# RH001_2.net
KiCad netlist of a schematic drawn in EAGLE
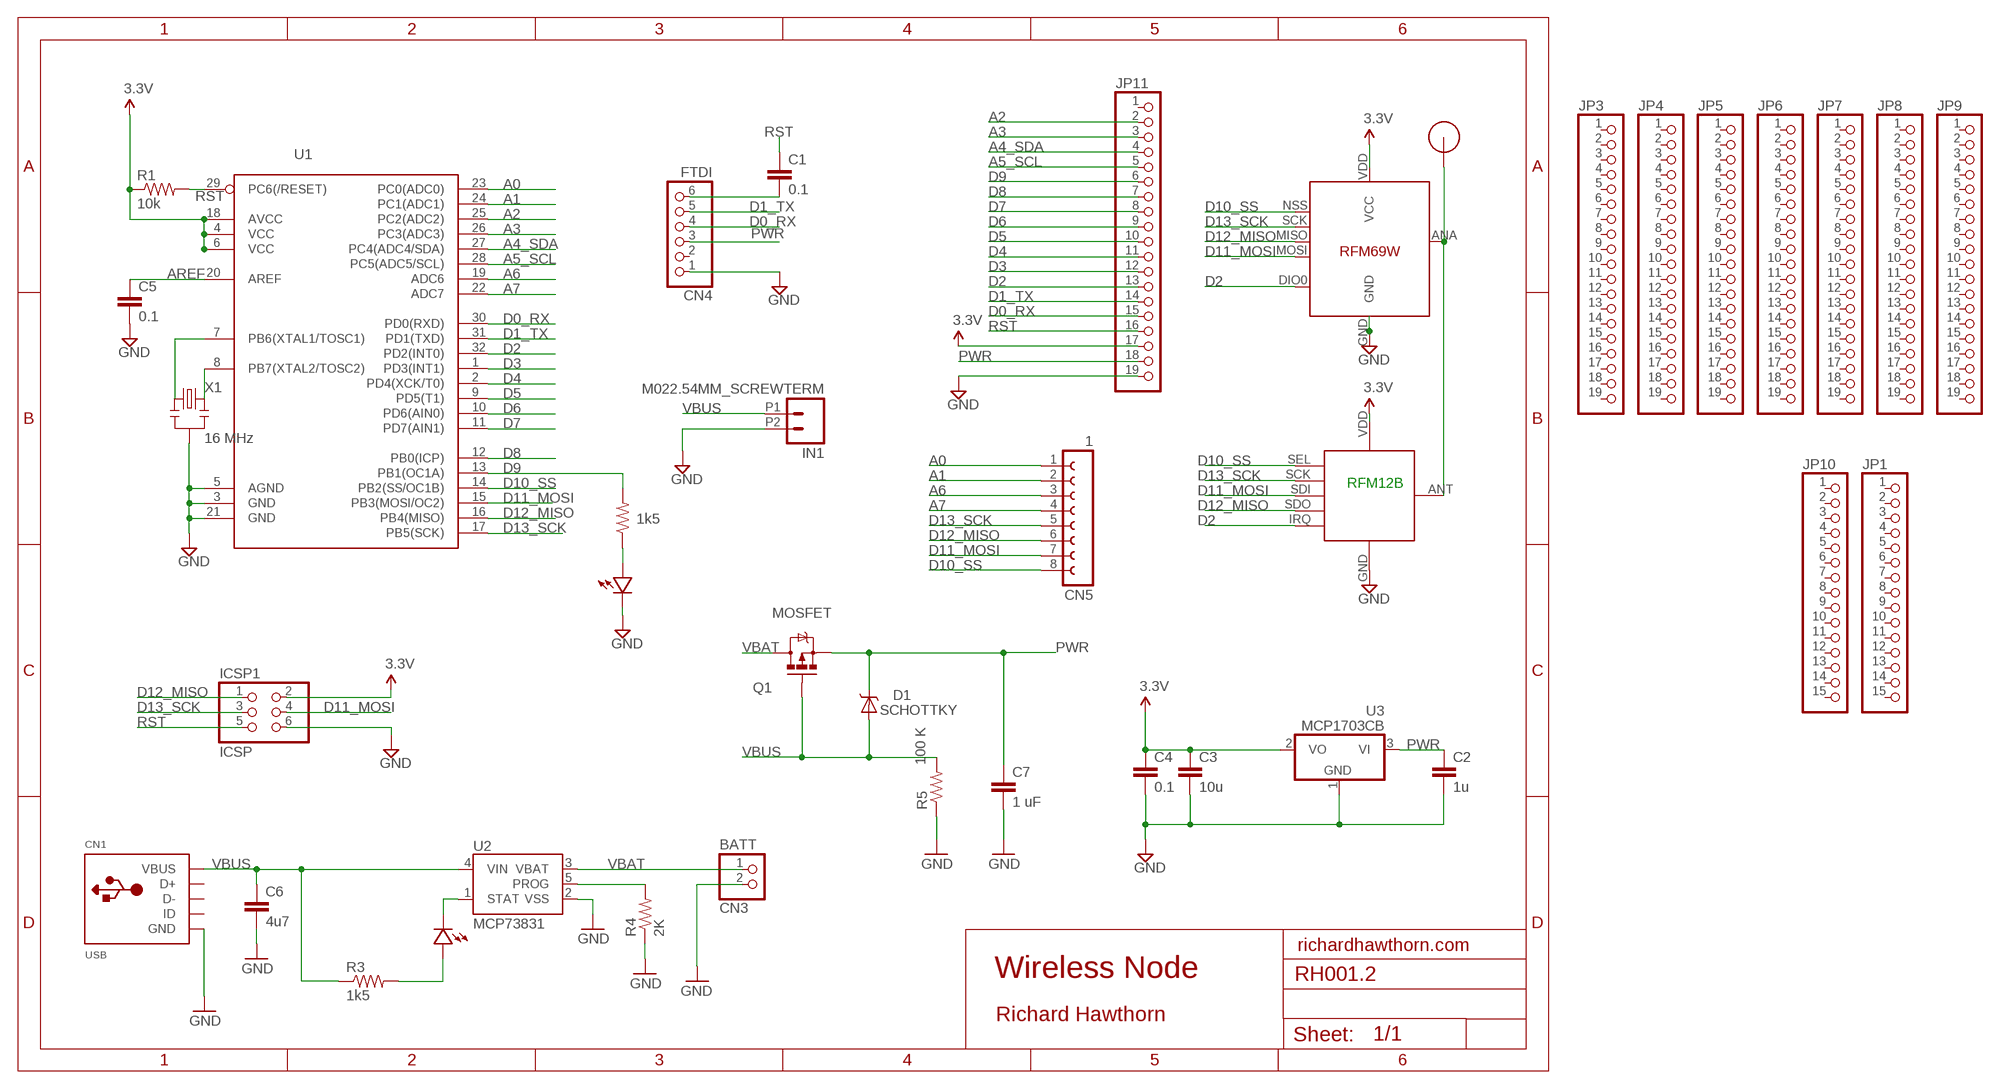
[diagram p0: schematic, sheet 1]

(export (version "E")
  (design (tool "Eeschema 10.0.6"))
  (components
    (comp (ref "C1")
      (value "0.1")
      (footprint "eagle-import:0603-CAP")
      (libsource (lib "eagle-import") (part "CAP0603-CAP"))
    )
    (comp (ref "C2")
      (value "1u")
      (footprint "eagle-import:0603-CAP")
      (libsource (lib "eagle-import") (part "CAP0603-CAP"))
    )
    (comp (ref "C3")
      (value "10u")
      (footprint "eagle-import:0805-CAP")
      (libsource (lib "eagle-import") (part "CAP0805-CAP"))
    )
    (comp (ref "C4")
      (value "0.1")
      (footprint "eagle-import:0603-CAP")
      (libsource (lib "eagle-import") (part "CAP0603-CAP"))
    )
    (comp (ref "C5")
      (value "0.1")
      (footprint "eagle-import:0603-CAP")
      (libsource (lib "eagle-import") (part "CAP0603-CAP"))
    )
    (comp (ref "C6")
      (value "4u7")
      (footprint "eagle-import:0603-CAP")
      (libsource (lib "eagle-import") (part "SparkFun_CAP0603-CAP"))
    )
    (comp (ref "C7")
      (value "1 uF")
      (footprint "eagle-import:0805")
      (libsource (lib "eagle-import") (part "SparkFun-Capacitors_CAP0805"))
    )
    (comp (ref "CN1")
      (value "USB")
      (footprint "eagle-import:USB-MINIB")
      (libsource (lib "eagle-import") (part "USBMINIB"))
    )
    (comp (ref "CN3")
      (value "BATT")
      (footprint "eagle-import:JST-PH-2-SMT-RA")
      (libsource (lib "eagle-import") (part "JST_2PIN-SMT-RA"))
    )
    (comp (ref "CN4")
      (value "FTDI")
      (footprint "eagle-import:1X06")
      (libsource (lib "eagle-import") (part "PINHD-1X6"))
    )
    (comp (ref "CN5")
      (value "1")
      (footprint "eagle-import:FE08")
      (libsource (lib "eagle-import") (part "FE08-1"))
    )
    (comp (ref "D1")
      (value "SCHOTTKY")
      (footprint "eagle-import:SMA-DIODE")
      (libsource (lib "eagle-import") (part "DIODE-SCHOTTKY_"))
    )
    (comp (ref "ICSP1")
      (value "ICSP")
      (footprint "eagle-import:2X03")
      (libsource (lib "eagle-import") (part "PINHD-2X3"))
    )
    (comp (ref "IN1")
      (value "M022.54MM_SCREWTERM")
      (footprint "eagle-import:1X02_2.54_SCREWTERM")
      (libsource (lib "eagle-import") (part "M022.54MM_SCREWTERM"))
    )
    (comp (ref "JP1")
      (value "PINHD-1X15")
      (footprint "eagle-import:1X15")
      (libsource (lib "eagle-import") (part "PINHD-1X15"))
    )
    (comp (ref "JP3")
      (value "PINHD-1X19")
      (footprint "eagle-import:1X19")
      (libsource (lib "eagle-import") (part "PINHD-1X19"))
    )
    (comp (ref "JP4")
      (value "PINHD-1X19")
      (footprint "eagle-import:1X19")
      (libsource (lib "eagle-import") (part "PINHD-1X19"))
    )
    (comp (ref "JP5")
      (value "PINHD-1X19")
      (footprint "eagle-import:1X19")
      (libsource (lib "eagle-import") (part "PINHD-1X19"))
    )
    (comp (ref "JP6")
      (value "PINHD-1X19")
      (footprint "eagle-import:1X19")
      (libsource (lib "eagle-import") (part "PINHD-1X19"))
    )
    (comp (ref "JP7")
      (value "PINHD-1X19")
      (footprint "eagle-import:1X19")
      (libsource (lib "eagle-import") (part "PINHD-1X19"))
    )
    (comp (ref "JP8")
      (value "PINHD-1X19")
      (footprint "eagle-import:1X19")
      (libsource (lib "eagle-import") (part "PINHD-1X19"))
    )
    (comp (ref "JP9")
      (value "PINHD-1X19")
      (footprint "eagle-import:1X19")
      (libsource (lib "eagle-import") (part "PINHD-1X19"))
    )
    (comp (ref "JP10")
      (value "PINHD-1X15")
      (footprint "eagle-import:1X15")
      (libsource (lib "eagle-import") (part "PINHD-1X15"))
    )
    (comp (ref "JP11")
      (value "PINHD-1X19")
      (footprint "eagle-import:1X19")
      (libsource (lib "eagle-import") (part "PINHD-1X19"))
    )
    (comp (ref "LED1")
      (value "LED0603")
      (footprint "eagle-import:0603-LED")
      (libsource (lib "eagle-import") (part "LED0603"))
    )
    (comp (ref "LED2")
      (value "LED0603")
      (footprint "eagle-import:0603-LED")
      (libsource (lib "eagle-import") (part "LED0603"))
    )
    (comp (ref "Q1")
      (value "MOSFET")
      (footprint "eagle-import:SOT23-3")
      (libsource (lib "eagle-import") (part "MOSFET-PCHANNELSMD"))
    )
    (comp (ref "R1")
      (value "10k")
      (footprint "eagle-import:0603-RES")
      (libsource (lib "eagle-import") (part "RESISTOR0603-RES"))
    )
    (comp (ref "R2")
      (value "1k5")
      (footprint "eagle-import:0603-RES")
      (libsource (lib "eagle-import") (part "RESISTOR0603-RES"))
    )
    (comp (ref "R3")
      (value "1k5")
      (footprint "eagle-import:0603-RES")
      (libsource (lib "eagle-import") (part "RESISTOR0603-RES"))
    )
    (comp (ref "R4")
      (value "2K")
      (footprint "eagle-import:0603-RES")
      (libsource (lib "eagle-import") (part "RESISTOR0603-RES"))
    )
    (comp (ref "R5")
      (value "100 K")
      (footprint "eagle-import:0805")
      (libsource (lib "eagle-import") (part "SparkFun-Resistors_RESISTOR0805-RES"))
    )
    (comp (ref "RF1")
      (value "RFM12B")
      (footprint "eagle-import:RFM12B-MINPADS")
      (libsource (lib "eagle-import") (part "RFM12B_MINPADS"))
    )
    (comp (ref "RF2")
      (value "RFM69")
      (footprint "eagle-import:RFM69W-MINPADS")
      (libsource (lib "eagle-import") (part "RFM69"))
    )
    (comp (ref "U$1")
      (value "RFM12B_ANTENNA")
      (footprint "eagle-import:RFM12B-ANTENNA")
      (libsource (lib "eagle-import") (part "RFM12B_ANTENNA"))
    )
    (comp (ref "U1")
      (value "ATMega-328")
      (footprint "eagle-import:TQFP32-08")
      (libsource (lib "eagle-import") (part "ATMEGA168/328TQFP32"))
    )
    (comp (ref "U2")
      (value "MCP73831")
      (footprint "eagle-import:SOT23-5")
      (libsource (lib "eagle-import") (part "MCP73831"))
    )
    (comp (ref "U3")
      (value "MCP1703CB")
      (footprint "eagle-import:SOT23")
      (libsource (lib "eagle-import") (part "MCP1703CB"))
    )
    (comp (ref "X1")
      (value "16 MHz")
      (footprint "eagle-import:RESONATOR-SMD")
      (libsource (lib "eagle-import") (part "RESONATORSMD"))
    )
  )
  (nets
    (net (code "1") (name "/A0") (class "Default")
      (node (ref "CN5") (pin "1") (pinfunction "1_1") (pintype "passive"))
      (node (ref "U1") (pin "23") (pinfunction "PC0(ADC0)_23") (pintype "bidirectional"))
    )
    (net (code "2") (name "/A1") (class "Default")
      (node (ref "CN5") (pin "2") (pinfunction "2_2") (pintype "passive"))
      (node (ref "U1") (pin "24") (pinfunction "PC1(ADC1)_24") (pintype "bidirectional"))
    )
    (net (code "3") (name "/A2") (class "Default")
      (node (ref "JP11") (pin "2") (pinfunction "2_2") (pintype "passive"))
      (node (ref "U1") (pin "25") (pinfunction "PC2(ADC2)_25") (pintype "bidirectional"))
    )
    (net (code "4") (name "/A3") (class "Default")
      (node (ref "JP11") (pin "3") (pinfunction "3_3") (pintype "passive"))
      (node (ref "U1") (pin "26") (pinfunction "PC3(ADC3)_26") (pintype "bidirectional"))
    )
    (net (code "5") (name "/A4_SDA") (class "Default")
      (node (ref "JP11") (pin "4") (pinfunction "4_4") (pintype "passive"))
      (node (ref "U1") (pin "27") (pinfunction "PC4(ADC4/SDA)_27") (pintype "bidirectional"))
    )
    (net (code "6") (name "/A5_SCL") (class "Default")
      (node (ref "JP11") (pin "5") (pinfunction "5_5") (pintype "passive"))
      (node (ref "U1") (pin "28") (pinfunction "PC5(ADC5/SCL)_28") (pintype "bidirectional"))
    )
    (net (code "7") (name "/A6") (class "Default")
      (node (ref "CN5") (pin "3") (pinfunction "3_3") (pintype "passive"))
      (node (ref "U1") (pin "19") (pinfunction "ADC6_19") (pintype "bidirectional"))
    )
    (net (code "8") (name "/A7") (class "Default")
      (node (ref "CN5") (pin "4") (pinfunction "4_4") (pintype "passive"))
      (node (ref "U1") (pin "22") (pinfunction "ADC7_22") (pintype "bidirectional"))
    )
    (net (code "9") (name "/AREF") (class "Default")
      (node (ref "C5") (pin "1") (pinfunction "1_1") (pintype "passive"))
      (node (ref "U1") (pin "20") (pinfunction "AREF_20") (pintype "bidirectional"))
    )
    (net (code "10") (name "/D0_RX") (class "Default")
      (node (ref "CN4") (pin "4") (pinfunction "4_4") (pintype "passive"))
      (node (ref "JP11") (pin "15") (pinfunction "15_15") (pintype "passive"))
      (node (ref "U1") (pin "30") (pinfunction "PD0(RXD)_30") (pintype "bidirectional"))
    )
    (net (code "11") (name "/D1_TX") (class "Default")
      (node (ref "CN4") (pin "5") (pinfunction "5_5") (pintype "passive"))
      (node (ref "JP11") (pin "14") (pinfunction "14_14") (pintype "passive"))
      (node (ref "U1") (pin "31") (pinfunction "PD1(TXD)_31") (pintype "bidirectional"))
    )
    (net (code "12") (name "/D2") (class "Default")
      (node (ref "JP11") (pin "13") (pinfunction "13_13") (pintype "passive"))
      (node (ref "RF1") (pin "IRQ") (pinfunction "IRQ_IRQ") (pintype "bidirectional"))
      (node (ref "RF2") (pin "DIO0") (pinfunction "DIO0_DIO0") (pintype "open_collector"))
      (node (ref "U1") (pin "32") (pinfunction "PD2(INT0)_32") (pintype "bidirectional"))
    )
    (net (code "13") (name "/D3") (class "Default")
      (node (ref "JP11") (pin "12") (pinfunction "12_12") (pintype "passive"))
      (node (ref "U1") (pin "1") (pinfunction "PD3(INT1)_1") (pintype "bidirectional"))
    )
    (net (code "14") (name "/D4") (class "Default")
      (node (ref "JP11") (pin "11") (pinfunction "11_11") (pintype "passive"))
      (node (ref "U1") (pin "2") (pinfunction "PD4(XCK/T0)_2") (pintype "bidirectional"))
    )
    (net (code "15") (name "/D5") (class "Default")
      (node (ref "JP11") (pin "10") (pinfunction "10_10") (pintype "passive"))
      (node (ref "U1") (pin "9") (pinfunction "PD5(T1)_9") (pintype "bidirectional"))
    )
    (net (code "16") (name "/D6") (class "Default")
      (node (ref "JP11") (pin "9") (pinfunction "9_9") (pintype "passive"))
      (node (ref "U1") (pin "10") (pinfunction "PD6(AIN0)_10") (pintype "bidirectional"))
    )
    (net (code "17") (name "/D7") (class "Default")
      (node (ref "JP11") (pin "8") (pinfunction "8_8") (pintype "passive"))
      (node (ref "U1") (pin "11") (pinfunction "PD7(AIN1)_11") (pintype "bidirectional"))
    )
    (net (code "18") (name "/D8") (class "Default")
      (node (ref "JP11") (pin "7") (pinfunction "7_7") (pintype "passive"))
      (node (ref "U1") (pin "12") (pinfunction "PB0(ICP)_12") (pintype "bidirectional"))
    )
    (net (code "19") (name "/D9") (class "Default")
      (node (ref "JP11") (pin "6") (pinfunction "6_6") (pintype "passive"))
      (node (ref "R2") (pin "2") (pinfunction "2_2") (pintype "passive"))
      (node (ref "U1") (pin "13") (pinfunction "PB1(OC1A)_13") (pintype "bidirectional"))
    )
    (net (code "20") (name "/D10_SS") (class "Default")
      (node (ref "CN5") (pin "8") (pinfunction "8_8") (pintype "passive"))
      (node (ref "RF1") (pin "SEL") (pinfunction "SEL_SEL") (pintype "bidirectional"))
      (node (ref "RF2") (pin "NSS") (pinfunction "SEL_NSS") (pintype "input"))
      (node (ref "U1") (pin "14") (pinfunction "PB2(SS/OC1B)_14") (pintype "bidirectional"))
    )
    (net (code "21") (name "/D11_MOSI") (class "Default")
      (node (ref "CN5") (pin "7") (pinfunction "7_7") (pintype "passive"))
      (node (ref "ICSP1") (pin "4") (pinfunction "4_4") (pintype "passive"))
      (node (ref "RF1") (pin "SDI") (pinfunction "SDI/MOSI_SDI") (pintype "bidirectional"))
      (node (ref "RF2") (pin "MOSI") (pinfunction "MOSI_MOSI") (pintype "output"))
      (node (ref "U1") (pin "15") (pinfunction "PB3(MOSI/OC2)_15") (pintype "bidirectional"))
    )
    (net (code "22") (name "/D12_MISO") (class "Default")
      (node (ref "CN5") (pin "6") (pinfunction "6_6") (pintype "passive"))
      (node (ref "ICSP1") (pin "1") (pinfunction "1_1") (pintype "passive"))
      (node (ref "RF1") (pin "SDO") (pinfunction "SDO/MISO_SDO") (pintype "bidirectional"))
      (node (ref "RF2") (pin "MISO") (pinfunction "MISO_MISO") (pintype "input"))
      (node (ref "U1") (pin "16") (pinfunction "PB4(MISO)_16") (pintype "bidirectional"))
    )
    (net (code "23") (name "/D13_SCK") (class "Default")
      (node (ref "CN5") (pin "5") (pinfunction "5_5") (pintype "passive"))
      (node (ref "ICSP1") (pin "3") (pinfunction "3_3") (pintype "passive"))
      (node (ref "RF1") (pin "SCK") (pinfunction "SCK_SCK") (pintype "bidirectional"))
      (node (ref "RF2") (pin "SCK") (pinfunction "SCK_SCK") (pintype "input"))
      (node (ref "U1") (pin "17") (pinfunction "PB5(SCK)_17") (pintype "bidirectional"))
    )
    (net (code "24") (name "/PWR") (class "Default")
      (node (ref "C2") (pin "1") (pinfunction "1_1") (pintype "passive"))
      (node (ref "C7") (pin "1") (pinfunction "1_1") (pintype "passive"))
      (node (ref "CN4") (pin "3") (pinfunction "3_3") (pintype "passive"))
      (node (ref "D1") (pin "C") (pinfunction "C_C") (pintype "passive"))
      (node (ref "JP11") (pin "18") (pinfunction "18_18") (pintype "passive"))
      (node (ref "Q1") (pin "2") (pinfunction "S_2") (pintype "passive"))
      (node (ref "U3") (pin "3") (pinfunction "VI_3") (pintype "input"))
    )
    (net (code "25") (name "/RST") (class "Default")
      (node (ref "C1") (pin "1") (pinfunction "1_1") (pintype "passive"))
      (node (ref "ICSP1") (pin "5") (pinfunction "5_5") (pintype "passive"))
      (node (ref "JP11") (pin "16") (pinfunction "16_16") (pintype "passive"))
      (node (ref "R1") (pin "2") (pinfunction "2_2") (pintype "passive"))
      (node (ref "U1") (pin "29") (pinfunction "PC6(/RESET)_29") (pintype "bidirectional"))
    )
    (net (code "26") (name "/VBAT") (class "Default")
      (node (ref "CN3") (pin "1") (pinfunction "2_1") (pintype "passive"))
      (node (ref "Q1") (pin "3") (pinfunction "D_3") (pintype "passive"))
      (node (ref "U2") (pin "3") (pinfunction "VBAT_3") (pintype "power_in"))
    )
    (net (code "27") (name "/VBUS") (class "Default")
      (node (ref "C6") (pin "1") (pinfunction "1_1") (pintype "passive"))
      (node (ref "CN1") (pin "VBUS") (pinfunction "VBUS_VBUS") (pintype "power_in"))
      (node (ref "D1") (pin "A") (pinfunction "A_A") (pintype "passive"))
      (node (ref "IN1") (pin "P1") (pinfunction "1_P1") (pintype "passive"))
      (node (ref "Q1") (pin "1") (pinfunction "G_1") (pintype "passive"))
      (node (ref "R3") (pin "1") (pinfunction "1_1") (pintype "passive"))
      (node (ref "R5") (pin "2") (pinfunction "2_2") (pintype "passive"))
      (node (ref "U2") (pin "4") (pinfunction "VIN_4") (pintype "power_in"))
    )
    (net (code "28") (name "3.3V") (class "Default")
      (node (ref "C3") (pin "1") (pinfunction "1_1") (pintype "passive"))
      (node (ref "C4") (pin "1") (pinfunction "1_1") (pintype "passive"))
      (node (ref "ICSP1") (pin "2") (pinfunction "2_2") (pintype "passive"))
      (node (ref "JP11") (pin "17") (pinfunction "17_17") (pintype "passive"))
      (node (ref "R1") (pin "1") (pinfunction "1_1") (pintype "passive"))
      (node (ref "RF1") (pin "VDD") (pinfunction "VDD_VDD") (pintype "bidirectional"))
      (node (ref "RF2") (pin "VDD") (pinfunction "VCC_VDD") (pintype "power_in"))
      (node (ref "U1") (pin "18") (pinfunction "AVCC_18") (pintype "bidirectional"))
      (node (ref "U1") (pin "4") (pinfunction "VCC_4") (pintype "bidirectional"))
      (node (ref "U1") (pin "6") (pinfunction "VCC_6") (pintype "bidirectional"))
      (node (ref "U3") (pin "2") (pinfunction "VO_2") (pintype "passive"))
    )
    (net (code "29") (name "GND") (class "Default")
      (node (ref "C2") (pin "2") (pinfunction "2_2") (pintype "passive"))
      (node (ref "C3") (pin "2") (pinfunction "2_2") (pintype "passive"))
      (node (ref "C4") (pin "2") (pinfunction "2_2") (pintype "passive"))
      (node (ref "C5") (pin "2") (pinfunction "2_2") (pintype "passive"))
      (node (ref "C6") (pin "2") (pinfunction "2_2") (pintype "passive"))
      (node (ref "C7") (pin "2") (pinfunction "2_2") (pintype "passive"))
      (node (ref "CN1") (pin "GND") (pinfunction "GND_GND") (pintype "power_in"))
      (node (ref "CN3") (pin "2") (pinfunction "1_2") (pintype "passive"))
      (node (ref "CN4") (pin "1") (pinfunction "1_1") (pintype "passive"))
      (node (ref "ICSP1") (pin "6") (pinfunction "6_6") (pintype "passive"))
      (node (ref "IN1") (pin "P2") (pinfunction "2_P2") (pintype "passive"))
      (node (ref "JP11") (pin "19") (pinfunction "19_19") (pintype "passive"))
      (node (ref "LED2") (pin "MINUS") (pinfunction "MINUS_MINUS") (pintype "passive"))
      (node (ref "R4") (pin "1") (pinfunction "1_1") (pintype "passive"))
      (node (ref "R5") (pin "1") (pinfunction "1_1") (pintype "passive"))
      (node (ref "RF1") (pin "GND") (pinfunction "GND_GND") (pintype "bidirectional"))
      (node (ref "RF2") (pin "GND") (pinfunction "GND_GND") (pintype "power_in"))
      (node (ref "U1") (pin "21") (pinfunction "GND_21") (pintype "bidirectional"))
      (node (ref "U1") (pin "3") (pinfunction "GND_3") (pintype "bidirectional"))
      (node (ref "U1") (pin "5") (pinfunction "AGND_5") (pintype "bidirectional"))
      (node (ref "U2") (pin "2") (pinfunction "VSS_2") (pintype "power_in"))
      (node (ref "U3") (pin "1") (pinfunction "GND_1") (pintype "passive"))
      (node (ref "X1") (pin "2") (pinfunction "2_2") (pintype "passive"))
    )
    (net (code "30") (name "Net-(C1-Pad2)") (class "Default")
      (node (ref "C1") (pin "2") (pinfunction "2_2") (pintype "passive"))
      (node (ref "CN4") (pin "6") (pinfunction "6_6") (pintype "passive"))
    )
    (net (code "31") (name "Net-(LED1-PadPLUS)") (class "Default")
      (node (ref "LED1") (pin "PLUS") (pinfunction "PLUS_PLUS") (pintype "passive"))
      (node (ref "R3") (pin "2") (pinfunction "2_2") (pintype "passive"))
    )
    (net (code "32") (name "Net-(LED2-PadPLUS)") (class "Default")
      (node (ref "LED2") (pin "PLUS") (pinfunction "PLUS_PLUS") (pintype "passive"))
      (node (ref "R2") (pin "1") (pinfunction "1_1") (pintype "passive"))
    )
    (net (code "33") (name "Net-(RF2-ANT)") (class "Default")
      (node (ref "RF1") (pin "ANT") (pinfunction "ANT_ANT") (pintype "bidirectional"))
      (node (ref "RF2") (pin "ANA") (pinfunction "ANT_ANA") (pintype "passive"))
      (node (ref "U$1") (pin "P$1") (pinfunction "1_P$1") (pintype "bidirectional"))
    )
    (net (code "34") (name "Net-(U1-PB6(XTAL1{slash}TOSC1))") (class "Default")
      (node (ref "U1") (pin "7") (pinfunction "PB6(XTAL1/TOSC1)_7") (pintype "bidirectional"))
      (node (ref "X1") (pin "1") (pinfunction "1_1") (pintype "passive"))
    )
    (net (code "35") (name "Net-(U1-PB7(XTAL2{slash}TOSC2))") (class "Default")
      (node (ref "U1") (pin "8") (pinfunction "PB7(XTAL2/TOSC2)_8") (pintype "bidirectional"))
      (node (ref "X1") (pin "3") (pinfunction "3_3") (pintype "passive"))
    )
    (net (code "36") (name "Net-(U2-PROG)") (class "Default")
      (node (ref "R4") (pin "2") (pinfunction "2_2") (pintype "passive"))
      (node (ref "U2") (pin "5") (pinfunction "PROG_5") (pintype "input"))
    )
    (net (code "37") (name "Net-(U2-STAT)") (class "Default")
      (node (ref "LED1") (pin "MINUS") (pinfunction "MINUS_MINUS") (pintype "passive"))
      (node (ref "U2") (pin "1") (pinfunction "STAT_1") (pintype "output"))
    )
    (net (code "38") (name "unconnected-(CN1-PadD+)") (class "Default")
      (node (ref "CN1") (pin "D+") (pinfunction "D+_D+") (pintype "bidirectional"))
    )
    (net (code "39") (name "unconnected-(CN1-PadD-)") (class "Default")
      (node (ref "CN1") (pin "D-") (pinfunction "D-_D-") (pintype "bidirectional"))
    )
    (net (code "40") (name "unconnected-(CN1-PadID)") (class "Default")
      (node (ref "CN1") (pin "ID") (pinfunction "ID_ID") (pintype "bidirectional"))
    )
    (net (code "41") (name "unconnected-(CN4-Pad2)") (class "Default")
      (node (ref "CN4") (pin "2") (pinfunction "2_2") (pintype "passive"))
    )
    (net (code "42") (name "unconnected-(JP1-Pad1)") (class "Default")
      (node (ref "JP1") (pin "1") (pinfunction "1_1") (pintype "passive"))
    )
    (net (code "43") (name "unconnected-(JP1-Pad2)") (class "Default")
      (node (ref "JP1") (pin "2") (pinfunction "2_2") (pintype "passive"))
    )
    (net (code "44") (name "unconnected-(JP1-Pad3)") (class "Default")
      (node (ref "JP1") (pin "3") (pinfunction "3_3") (pintype "passive"))
    )
    (net (code "45") (name "unconnected-(JP1-Pad4)") (class "Default")
      (node (ref "JP1") (pin "4") (pinfunction "4_4") (pintype "passive"))
    )
    (net (code "46") (name "unconnected-(JP1-Pad5)") (class "Default")
      (node (ref "JP1") (pin "5") (pinfunction "5_5") (pintype "passive"))
    )
    (net (code "47") (name "unconnected-(JP1-Pad6)") (class "Default")
      (node (ref "JP1") (pin "6") (pinfunction "6_6") (pintype "passive"))
    )
    (net (code "48") (name "unconnected-(JP1-Pad7)") (class "Default")
      (node (ref "JP1") (pin "7") (pinfunction "7_7") (pintype "passive"))
    )
    (net (code "49") (name "unconnected-(JP1-Pad8)") (class "Default")
      (node (ref "JP1") (pin "8") (pinfunction "8_8") (pintype "passive"))
    )
    (net (code "50") (name "unconnected-(JP1-Pad9)") (class "Default")
      (node (ref "JP1") (pin "9") (pinfunction "9_9") (pintype "passive"))
    )
    (net (code "51") (name "unconnected-(JP1-Pad10)") (class "Default")
      (node (ref "JP1") (pin "10") (pinfunction "10_10") (pintype "passive"))
    )
    (net (code "52") (name "unconnected-(JP1-Pad11)") (class "Default")
      (node (ref "JP1") (pin "11") (pinfunction "11_11") (pintype "passive"))
    )
    (net (code "53") (name "unconnected-(JP1-Pad12)") (class "Default")
      (node (ref "JP1") (pin "12") (pinfunction "12_12") (pintype "passive"))
    )
    (net (code "54") (name "unconnected-(JP1-Pad13)") (class "Default")
      (node (ref "JP1") (pin "13") (pinfunction "13_13") (pintype "passive"))
    )
    (net (code "55") (name "unconnected-(JP1-Pad14)") (class "Default")
      (node (ref "JP1") (pin "14") (pinfunction "14_14") (pintype "passive"))
    )
    (net (code "56") (name "unconnected-(JP1-Pad15)") (class "Default")
      (node (ref "JP1") (pin "15") (pinfunction "15_15") (pintype "passive"))
    )
    (net (code "57") (name "unconnected-(JP3-Pad1)") (class "Default")
      (node (ref "JP3") (pin "1") (pinfunction "1_1") (pintype "passive"))
    )
    (net (code "58") (name "unconnected-(JP3-Pad2)") (class "Default")
      (node (ref "JP3") (pin "2") (pinfunction "2_2") (pintype "passive"))
    )
    (net (code "59") (name "unconnected-(JP3-Pad3)") (class "Default")
      (node (ref "JP3") (pin "3") (pinfunction "3_3") (pintype "passive"))
    )
    (net (code "60") (name "unconnected-(JP3-Pad4)") (class "Default")
      (node (ref "JP3") (pin "4") (pinfunction "4_4") (pintype "passive"))
    )
    (net (code "61") (name "unconnected-(JP3-Pad5)") (class "Default")
      (node (ref "JP3") (pin "5") (pinfunction "5_5") (pintype "passive"))
    )
    (net (code "62") (name "unconnected-(JP3-Pad6)") (class "Default")
      (node (ref "JP3") (pin "6") (pinfunction "6_6") (pintype "passive"))
    )
    (net (code "63") (name "unconnected-(JP3-Pad7)") (class "Default")
      (node (ref "JP3") (pin "7") (pinfunction "7_7") (pintype "passive"))
    )
    (net (code "64") (name "unconnected-(JP3-Pad8)") (class "Default")
      (node (ref "JP3") (pin "8") (pinfunction "8_8") (pintype "passive"))
    )
    (net (code "65") (name "unconnected-(JP3-Pad9)") (class "Default")
      (node (ref "JP3") (pin "9") (pinfunction "9_9") (pintype "passive"))
    )
    (net (code "66") (name "unconnected-(JP3-Pad10)") (class "Default")
      (node (ref "JP3") (pin "10") (pinfunction "10_10") (pintype "passive"))
    )
    (net (code "67") (name "unconnected-(JP3-Pad11)") (class "Default")
      (node (ref "JP3") (pin "11") (pinfunction "11_11") (pintype "passive"))
    )
    (net (code "68") (name "unconnected-(JP3-Pad12)") (class "Default")
      (node (ref "JP3") (pin "12") (pinfunction "12_12") (pintype "passive"))
    )
    (net (code "69") (name "unconnected-(JP3-Pad13)") (class "Default")
      (node (ref "JP3") (pin "13") (pinfunction "13_13") (pintype "passive"))
    )
    (net (code "70") (name "unconnected-(JP3-Pad14)") (class "Default")
      (node (ref "JP3") (pin "14") (pinfunction "14_14") (pintype "passive"))
    )
    (net (code "71") (name "unconnected-(JP3-Pad15)") (class "Default")
      (node (ref "JP3") (pin "15") (pinfunction "15_15") (pintype "passive"))
    )
    (net (code "72") (name "unconnected-(JP3-Pad16)") (class "Default")
      (node (ref "JP3") (pin "16") (pinfunction "16_16") (pintype "passive"))
    )
    (net (code "73") (name "unconnected-(JP3-Pad17)") (class "Default")
      (node (ref "JP3") (pin "17") (pinfunction "17_17") (pintype "passive"))
    )
    (net (code "74") (name "unconnected-(JP3-Pad18)") (class "Default")
      (node (ref "JP3") (pin "18") (pinfunction "18_18") (pintype "passive"))
    )
    (net (code "75") (name "unconnected-(JP3-Pad19)") (class "Default")
      (node (ref "JP3") (pin "19") (pinfunction "19_19") (pintype "passive"))
    )
    (net (code "76") (name "unconnected-(JP4-Pad1)") (class "Default")
      (node (ref "JP4") (pin "1") (pinfunction "1_1") (pintype "passive"))
    )
    (net (code "77") (name "unconnected-(JP4-Pad2)") (class "Default")
      (node (ref "JP4") (pin "2") (pinfunction "2_2") (pintype "passive"))
    )
    (net (code "78") (name "unconnected-(JP4-Pad3)") (class "Default")
      (node (ref "JP4") (pin "3") (pinfunction "3_3") (pintype "passive"))
    )
    (net (code "79") (name "unconnected-(JP4-Pad4)") (class "Default")
      (node (ref "JP4") (pin "4") (pinfunction "4_4") (pintype "passive"))
    )
    (net (code "80") (name "unconnected-(JP4-Pad5)") (class "Default")
      (node (ref "JP4") (pin "5") (pinfunction "5_5") (pintype "passive"))
    )
    (net (code "81") (name "unconnected-(JP4-Pad6)") (class "Default")
      (node (ref "JP4") (pin "6") (pinfunction "6_6") (pintype "passive"))
    )
    (net (code "82") (name "unconnected-(JP4-Pad7)") (class "Default")
      (node (ref "JP4") (pin "7") (pinfunction "7_7") (pintype "passive"))
    )
    (net (code "83") (name "unconnected-(JP4-Pad8)") (class "Default")
      (node (ref "JP4") (pin "8") (pinfunction "8_8") (pintype "passive"))
    )
    (net (code "84") (name "unconnected-(JP4-Pad9)") (class "Default")
      (node (ref "JP4") (pin "9") (pinfunction "9_9") (pintype "passive"))
    )
    (net (code "85") (name "unconnected-(JP4-Pad10)") (class "Default")
      (node (ref "JP4") (pin "10") (pinfunction "10_10") (pintype "passive"))
    )
    (net (code "86") (name "unconnected-(JP4-Pad11)") (class "Default")
      (node (ref "JP4") (pin "11") (pinfunction "11_11") (pintype "passive"))
    )
    (net (code "87") (name "unconnected-(JP4-Pad12)") (class "Default")
      (node (ref "JP4") (pin "12") (pinfunction "12_12") (pintype "passive"))
    )
    (net (code "88") (name "unconnected-(JP4-Pad13)") (class "Default")
      (node (ref "JP4") (pin "13") (pinfunction "13_13") (pintype "passive"))
    )
    (net (code "89") (name "unconnected-(JP4-Pad14)") (class "Default")
      (node (ref "JP4") (pin "14") (pinfunction "14_14") (pintype "passive"))
    )
    (net (code "90") (name "unconnected-(JP4-Pad15)") (class "Default")
      (node (ref "JP4") (pin "15") (pinfunction "15_15") (pintype "passive"))
    )
    (net (code "91") (name "unconnected-(JP4-Pad16)") (class "Default")
      (node (ref "JP4") (pin "16") (pinfunction "16_16") (pintype "passive"))
    )
    (net (code "92") (name "unconnected-(JP4-Pad17)") (class "Default")
      (node (ref "JP4") (pin "17") (pinfunction "17_17") (pintype "passive"))
    )
    (net (code "93") (name "unconnected-(JP4-Pad18)") (class "Default")
      (node (ref "JP4") (pin "18") (pinfunction "18_18") (pintype "passive"))
    )
    (net (code "94") (name "unconnected-(JP4-Pad19)") (class "Default")
      (node (ref "JP4") (pin "19") (pinfunction "19_19") (pintype "passive"))
    )
    (net (code "95") (name "unconnected-(JP5-Pad1)") (class "Default")
      (node (ref "JP5") (pin "1") (pinfunction "1_1") (pintype "passive"))
    )
    (net (code "96") (name "unconnected-(JP5-Pad2)") (class "Default")
      (node (ref "JP5") (pin "2") (pinfunction "2_2") (pintype "passive"))
    )
    (net (code "97") (name "unconnected-(JP5-Pad3)") (class "Default")
      (node (ref "JP5") (pin "3") (pinfunction "3_3") (pintype "passive"))
    )
    (net (code "98") (name "unconnected-(JP5-Pad4)") (class "Default")
      (node (ref "JP5") (pin "4") (pinfunction "4_4") (pintype "passive"))
    )
    (net (code "99") (name "unconnected-(JP5-Pad5)") (class "Default")
      (node (ref "JP5") (pin "5") (pinfunction "5_5") (pintype "passive"))
    )
    (net (code "100") (name "unconnected-(JP5-Pad6)") (class "Default")
      (node (ref "JP5") (pin "6") (pinfunction "6_6") (pintype "passive"))
    )
    (net (code "101") (name "unconnected-(JP5-Pad7)") (class "Default")
      (node (ref "JP5") (pin "7") (pinfunction "7_7") (pintype "passive"))
    )
    (net (code "102") (name "unconnected-(JP5-Pad8)") (class "Default")
      (node (ref "JP5") (pin "8") (pinfunction "8_8") (pintype "passive"))
    )
    (net (code "103") (name "unconnected-(JP5-Pad9)") (class "Default")
      (node (ref "JP5") (pin "9") (pinfunction "9_9") (pintype "passive"))
    )
    (net (code "104") (name "unconnected-(JP5-Pad10)") (class "Default")
      (node (ref "JP5") (pin "10") (pinfunction "10_10") (pintype "passive"))
    )
    (net (code "105") (name "unconnected-(JP5-Pad11)") (class "Default")
      (node (ref "JP5") (pin "11") (pinfunction "11_11") (pintype "passive"))
    )
    (net (code "106") (name "unconnected-(JP5-Pad12)") (class "Default")
      (node (ref "JP5") (pin "12") (pinfunction "12_12") (pintype "passive"))
    )
    (net (code "107") (name "unconnected-(JP5-Pad13)") (class "Default")
      (node (ref "JP5") (pin "13") (pinfunction "13_13") (pintype "passive"))
    )
    (net (code "108") (name "unconnected-(JP5-Pad14)") (class "Default")
      (node (ref "JP5") (pin "14") (pinfunction "14_14") (pintype "passive"))
    )
    (net (code "109") (name "unconnected-(JP5-Pad15)") (class "Default")
      (node (ref "JP5") (pin "15") (pinfunction "15_15") (pintype "passive"))
    )
    (net (code "110") (name "unconnected-(JP5-Pad16)") (class "Default")
      (node (ref "JP5") (pin "16") (pinfunction "16_16") (pintype "passive"))
    )
    (net (code "111") (name "unconnected-(JP5-Pad17)") (class "Default")
      (node (ref "JP5") (pin "17") (pinfunction "17_17") (pintype "passive"))
    )
    (net (code "112") (name "unconnected-(JP5-Pad18)") (class "Default")
      (node (ref "JP5") (pin "18") (pinfunction "18_18") (pintype "passive"))
    )
    (net (code "113") (name "unconnected-(JP5-Pad19)") (class "Default")
      (node (ref "JP5") (pin "19") (pinfunction "19_19") (pintype "passive"))
    )
    (net (code "114") (name "unconnected-(JP6-Pad1)") (class "Default")
      (node (ref "JP6") (pin "1") (pinfunction "1_1") (pintype "passive"))
    )
    (net (code "115") (name "unconnected-(JP6-Pad2)") (class "Default")
      (node (ref "JP6") (pin "2") (pinfunction "2_2") (pintype "passive"))
    )
    (net (code "116") (name "unconnected-(JP6-Pad3)") (class "Default")
      (node (ref "JP6") (pin "3") (pinfunction "3_3") (pintype "passive"))
    )
    (net (code "117") (name "unconnected-(JP6-Pad4)") (class "Default")
      (node (ref "JP6") (pin "4") (pinfunction "4_4") (pintype "passive"))
    )
    (net (code "118") (name "unconnected-(JP6-Pad5)") (class "Default")
      (node (ref "JP6") (pin "5") (pinfunction "5_5") (pintype "passive"))
    )
    (net (code "119") (name "unconnected-(JP6-Pad6)") (class "Default")
      (node (ref "JP6") (pin "6") (pinfunction "6_6") (pintype "passive"))
    )
    (net (code "120") (name "unconnected-(JP6-Pad7)") (class "Default")
      (node (ref "JP6") (pin "7") (pinfunction "7_7") (pintype "passive"))
    )
    (net (code "121") (name "unconnected-(JP6-Pad8)") (class "Default")
      (node (ref "JP6") (pin "8") (pinfunction "8_8") (pintype "passive"))
    )
    (net (code "122") (name "unconnected-(JP6-Pad9)") (class "Default")
      (node (ref "JP6") (pin "9") (pinfunction "9_9") (pintype "passive"))
    )
    (net (code "123") (name "unconnected-(JP6-Pad10)") (class "Default")
      (node (ref "JP6") (pin "10") (pinfunction "10_10") (pintype "passive"))
    )
    (net (code "124") (name "unconnected-(JP6-Pad11)") (class "Default")
      (node (ref "JP6") (pin "11") (pinfunction "11_11") (pintype "passive"))
    )
    (net (code "125") (name "unconnected-(JP6-Pad12)") (class "Default")
      (node (ref "JP6") (pin "12") (pinfunction "12_12") (pintype "passive"))
    )
    (net (code "126") (name "unconnected-(JP6-Pad13)") (class "Default")
      (node (ref "JP6") (pin "13") (pinfunction "13_13") (pintype "passive"))
    )
    (net (code "127") (name "unconnected-(JP6-Pad14)") (class "Default")
      (node (ref "JP6") (pin "14") (pinfunction "14_14") (pintype "passive"))
    )
    (net (code "128") (name "unconnected-(JP6-Pad15)") (class "Default")
      (node (ref "JP6") (pin "15") (pinfunction "15_15") (pintype "passive"))
    )
    (net (code "129") (name "unconnected-(JP6-Pad16)") (class "Default")
      (node (ref "JP6") (pin "16") (pinfunction "16_16") (pintype "passive"))
    )
    (net (code "130") (name "unconnected-(JP6-Pad17)") (class "Default")
      (node (ref "JP6") (pin "17") (pinfunction "17_17") (pintype "passive"))
    )
    (net (code "131") (name "unconnected-(JP6-Pad18)") (class "Default")
      (node (ref "JP6") (pin "18") (pinfunction "18_18") (pintype "passive"))
    )
    (net (code "132") (name "unconnected-(JP6-Pad19)") (class "Default")
      (node (ref "JP6") (pin "19") (pinfunction "19_19") (pintype "passive"))
    )
    (net (code "133") (name "unconnected-(JP7-Pad1)") (class "Default")
      (node (ref "JP7") (pin "1") (pinfunction "1_1") (pintype "passive"))
    )
    (net (code "134") (name "unconnected-(JP7-Pad2)") (class "Default")
      (node (ref "JP7") (pin "2") (pinfunction "2_2") (pintype "passive"))
    )
    (net (code "135") (name "unconnected-(JP7-Pad3)") (class "Default")
      (node (ref "JP7") (pin "3") (pinfunction "3_3") (pintype "passive"))
    )
    (net (code "136") (name "unconnected-(JP7-Pad4)") (class "Default")
      (node (ref "JP7") (pin "4") (pinfunction "4_4") (pintype "passive"))
    )
    (net (code "137") (name "unconnected-(JP7-Pad5)") (class "Default")
      (node (ref "JP7") (pin "5") (pinfunction "5_5") (pintype "passive"))
    )
    (net (code "138") (name "unconnected-(JP7-Pad6)") (class "Default")
      (node (ref "JP7") (pin "6") (pinfunction "6_6") (pintype "passive"))
    )
    (net (code "139") (name "unconnected-(JP7-Pad7)") (class "Default")
      (node (ref "JP7") (pin "7") (pinfunction "7_7") (pintype "passive"))
    )
    (net (code "140") (name "unconnected-(JP7-Pad8)") (class "Default")
      (node (ref "JP7") (pin "8") (pinfunction "8_8") (pintype "passive"))
    )
    (net (code "141") (name "unconnected-(JP7-Pad9)") (class "Default")
      (node (ref "JP7") (pin "9") (pinfunction "9_9") (pintype "passive"))
    )
    (net (code "142") (name "unconnected-(JP7-Pad10)") (class "Default")
      (node (ref "JP7") (pin "10") (pinfunction "10_10") (pintype "passive"))
    )
    (net (code "143") (name "unconnected-(JP7-Pad11)") (class "Default")
      (node (ref "JP7") (pin "11") (pinfunction "11_11") (pintype "passive"))
    )
    (net (code "144") (name "unconnected-(JP7-Pad12)") (class "Default")
      (node (ref "JP7") (pin "12") (pinfunction "12_12") (pintype "passive"))
    )
    (net (code "145") (name "unconnected-(JP7-Pad13)") (class "Default")
      (node (ref "JP7") (pin "13") (pinfunction "13_13") (pintype "passive"))
    )
    (net (code "146") (name "unconnected-(JP7-Pad14)") (class "Default")
      (node (ref "JP7") (pin "14") (pinfunction "14_14") (pintype "passive"))
    )
    (net (code "147") (name "unconnected-(JP7-Pad15)") (class "Default")
      (node (ref "JP7") (pin "15") (pinfunction "15_15") (pintype "passive"))
    )
    (net (code "148") (name "unconnected-(JP7-Pad16)") (class "Default")
      (node (ref "JP7") (pin "16") (pinfunction "16_16") (pintype "passive"))
    )
    (net (code "149") (name "unconnected-(JP7-Pad17)") (class "Default")
      (node (ref "JP7") (pin "17") (pinfunction "17_17") (pintype "passive"))
    )
    (net (code "150") (name "unconnected-(JP7-Pad18)") (class "Default")
      (node (ref "JP7") (pin "18") (pinfunction "18_18") (pintype "passive"))
    )
    (net (code "151") (name "unconnected-(JP7-Pad19)") (class "Default")
      (node (ref "JP7") (pin "19") (pinfunction "19_19") (pintype "passive"))
    )
    (net (code "152") (name "unconnected-(JP8-Pad1)") (class "Default")
      (node (ref "JP8") (pin "1") (pinfunction "1_1") (pintype "passive"))
    )
    (net (code "153") (name "unconnected-(JP8-Pad2)") (class "Default")
      (node (ref "JP8") (pin "2") (pinfunction "2_2") (pintype "passive"))
    )
    (net (code "154") (name "unconnected-(JP8-Pad3)") (class "Default")
      (node (ref "JP8") (pin "3") (pinfunction "3_3") (pintype "passive"))
    )
    (net (code "155") (name "unconnected-(JP8-Pad4)") (class "Default")
      (node (ref "JP8") (pin "4") (pinfunction "4_4") (pintype "passive"))
    )
    (net (code "156") (name "unconnected-(JP8-Pad5)") (class "Default")
      (node (ref "JP8") (pin "5") (pinfunction "5_5") (pintype "passive"))
    )
    (net (code "157") (name "unconnected-(JP8-Pad6)") (class "Default")
      (node (ref "JP8") (pin "6") (pinfunction "6_6") (pintype "passive"))
    )
    (net (code "158") (name "unconnected-(JP8-Pad7)") (class "Default")
      (node (ref "JP8") (pin "7") (pinfunction "7_7") (pintype "passive"))
    )
    (net (code "159") (name "unconnected-(JP8-Pad8)") (class "Default")
      (node (ref "JP8") (pin "8") (pinfunction "8_8") (pintype "passive"))
    )
    (net (code "160") (name "unconnected-(JP8-Pad9)") (class "Default")
      (node (ref "JP8") (pin "9") (pinfunction "9_9") (pintype "passive"))
    )
    (net (code "161") (name "unconnected-(JP8-Pad10)") (class "Default")
      (node (ref "JP8") (pin "10") (pinfunction "10_10") (pintype "passive"))
    )
    (net (code "162") (name "unconnected-(JP8-Pad11)") (class "Default")
      (node (ref "JP8") (pin "11") (pinfunction "11_11") (pintype "passive"))
    )
    (net (code "163") (name "unconnected-(JP8-Pad12)") (class "Default")
      (node (ref "JP8") (pin "12") (pinfunction "12_12") (pintype "passive"))
    )
    (net (code "164") (name "unconnected-(JP8-Pad13)") (class "Default")
      (node (ref "JP8") (pin "13") (pinfunction "13_13") (pintype "passive"))
    )
    (net (code "165") (name "unconnected-(JP8-Pad14)") (class "Default")
      (node (ref "JP8") (pin "14") (pinfunction "14_14") (pintype "passive"))
    )
    (net (code "166") (name "unconnected-(JP8-Pad15)") (class "Default")
      (node (ref "JP8") (pin "15") (pinfunction "15_15") (pintype "passive"))
    )
    (net (code "167") (name "unconnected-(JP8-Pad16)") (class "Default")
      (node (ref "JP8") (pin "16") (pinfunction "16_16") (pintype "passive"))
    )
    (net (code "168") (name "unconnected-(JP8-Pad17)") (class "Default")
      (node (ref "JP8") (pin "17") (pinfunction "17_17") (pintype "passive"))
    )
    (net (code "169") (name "unconnected-(JP8-Pad18)") (class "Default")
      (node (ref "JP8") (pin "18") (pinfunction "18_18") (pintype "passive"))
    )
    (net (code "170") (name "unconnected-(JP8-Pad19)") (class "Default")
      (node (ref "JP8") (pin "19") (pinfunction "19_19") (pintype "passive"))
    )
    (net (code "171") (name "unconnected-(JP9-Pad1)") (class "Default")
      (node (ref "JP9") (pin "1") (pinfunction "1_1") (pintype "passive"))
    )
    (net (code "172") (name "unconnected-(JP9-Pad2)") (class "Default")
      (node (ref "JP9") (pin "2") (pinfunction "2_2") (pintype "passive"))
    )
    (net (code "173") (name "unconnected-(JP9-Pad3)") (class "Default")
      (node (ref "JP9") (pin "3") (pinfunction "3_3") (pintype "passive"))
    )
    (net (code "174") (name "unconnected-(JP9-Pad4)") (class "Default")
      (node (ref "JP9") (pin "4") (pinfunction "4_4") (pintype "passive"))
    )
    (net (code "175") (name "unconnected-(JP9-Pad5)") (class "Default")
      (node (ref "JP9") (pin "5") (pinfunction "5_5") (pintype "passive"))
    )
    (net (code "176") (name "unconnected-(JP9-Pad6)") (class "Default")
      (node (ref "JP9") (pin "6") (pinfunction "6_6") (pintype "passive"))
    )
    (net (code "177") (name "unconnected-(JP9-Pad7)") (class "Default")
      (node (ref "JP9") (pin "7") (pinfunction "7_7") (pintype "passive"))
    )
    (net (code "178") (name "unconnected-(JP9-Pad8)") (class "Default")
      (node (ref "JP9") (pin "8") (pinfunction "8_8") (pintype "passive"))
    )
    (net (code "179") (name "unconnected-(JP9-Pad9)") (class "Default")
      (node (ref "JP9") (pin "9") (pinfunction "9_9") (pintype "passive"))
    )
    (net (code "180") (name "unconnected-(JP9-Pad10)") (class "Default")
      (node (ref "JP9") (pin "10") (pinfunction "10_10") (pintype "passive"))
    )
    (net (code "181") (name "unconnected-(JP9-Pad11)") (class "Default")
      (node (ref "JP9") (pin "11") (pinfunction "11_11") (pintype "passive"))
    )
    (net (code "182") (name "unconnected-(JP9-Pad12)") (class "Default")
      (node (ref "JP9") (pin "12") (pinfunction "12_12") (pintype "passive"))
    )
    (net (code "183") (name "unconnected-(JP9-Pad13)") (class "Default")
      (node (ref "JP9") (pin "13") (pinfunction "13_13") (pintype "passive"))
    )
    (net (code "184") (name "unconnected-(JP9-Pad14)") (class "Default")
      (node (ref "JP9") (pin "14") (pinfunction "14_14") (pintype "passive"))
    )
    (net (code "185") (name "unconnected-(JP9-Pad15)") (class "Default")
      (node (ref "JP9") (pin "15") (pinfunction "15_15") (pintype "passive"))
    )
    (net (code "186") (name "unconnected-(JP9-Pad16)") (class "Default")
      (node (ref "JP9") (pin "16") (pinfunction "16_16") (pintype "passive"))
    )
    (net (code "187") (name "unconnected-(JP9-Pad17)") (class "Default")
      (node (ref "JP9") (pin "17") (pinfunction "17_17") (pintype "passive"))
    )
    (net (code "188") (name "unconnected-(JP9-Pad18)") (class "Default")
      (node (ref "JP9") (pin "18") (pinfunction "18_18") (pintype "passive"))
    )
    (net (code "189") (name "unconnected-(JP9-Pad19)") (class "Default")
      (node (ref "JP9") (pin "19") (pinfunction "19_19") (pintype "passive"))
    )
    (net (code "190") (name "unconnected-(JP10-Pad1)") (class "Default")
      (node (ref "JP10") (pin "1") (pinfunction "1_1") (pintype "passive"))
    )
    (net (code "191") (name "unconnected-(JP10-Pad2)") (class "Default")
      (node (ref "JP10") (pin "2") (pinfunction "2_2") (pintype "passive"))
    )
    (net (code "192") (name "unconnected-(JP10-Pad3)") (class "Default")
      (node (ref "JP10") (pin "3") (pinfunction "3_3") (pintype "passive"))
    )
    (net (code "193") (name "unconnected-(JP10-Pad4)") (class "Default")
      (node (ref "JP10") (pin "4") (pinfunction "4_4") (pintype "passive"))
    )
    (net (code "194") (name "unconnected-(JP10-Pad5)") (class "Default")
      (node (ref "JP10") (pin "5") (pinfunction "5_5") (pintype "passive"))
    )
    (net (code "195") (name "unconnected-(JP10-Pad6)") (class "Default")
      (node (ref "JP10") (pin "6") (pinfunction "6_6") (pintype "passive"))
    )
    (net (code "196") (name "unconnected-(JP10-Pad7)") (class "Default")
      (node (ref "JP10") (pin "7") (pinfunction "7_7") (pintype "passive"))
    )
    (net (code "197") (name "unconnected-(JP10-Pad8)") (class "Default")
      (node (ref "JP10") (pin "8") (pinfunction "8_8") (pintype "passive"))
    )
    (net (code "198") (name "unconnected-(JP10-Pad9)") (class "Default")
      (node (ref "JP10") (pin "9") (pinfunction "9_9") (pintype "passive"))
    )
    (net (code "199") (name "unconnected-(JP10-Pad10)") (class "Default")
      (node (ref "JP10") (pin "10") (pinfunction "10_10") (pintype "passive"))
    )
    (net (code "200") (name "unconnected-(JP10-Pad11)") (class "Default")
      (node (ref "JP10") (pin "11") (pinfunction "11_11") (pintype "passive"))
    )
    (net (code "201") (name "unconnected-(JP10-Pad12)") (class "Default")
      (node (ref "JP10") (pin "12") (pinfunction "12_12") (pintype "passive"))
    )
    (net (code "202") (name "unconnected-(JP10-Pad13)") (class "Default")
      (node (ref "JP10") (pin "13") (pinfunction "13_13") (pintype "passive"))
    )
    (net (code "203") (name "unconnected-(JP10-Pad14)") (class "Default")
      (node (ref "JP10") (pin "14") (pinfunction "14_14") (pintype "passive"))
    )
    (net (code "204") (name "unconnected-(JP10-Pad15)") (class "Default")
      (node (ref "JP10") (pin "15") (pinfunction "15_15") (pintype "passive"))
    )
    (net (code "205") (name "unconnected-(JP11-Pad1)") (class "Default")
      (node (ref "JP11") (pin "1") (pinfunction "1_1") (pintype "passive"))
    )
  )
)
